# elysium_v0_1.net
KiCad netlist of a schematic drawn in EAGLE
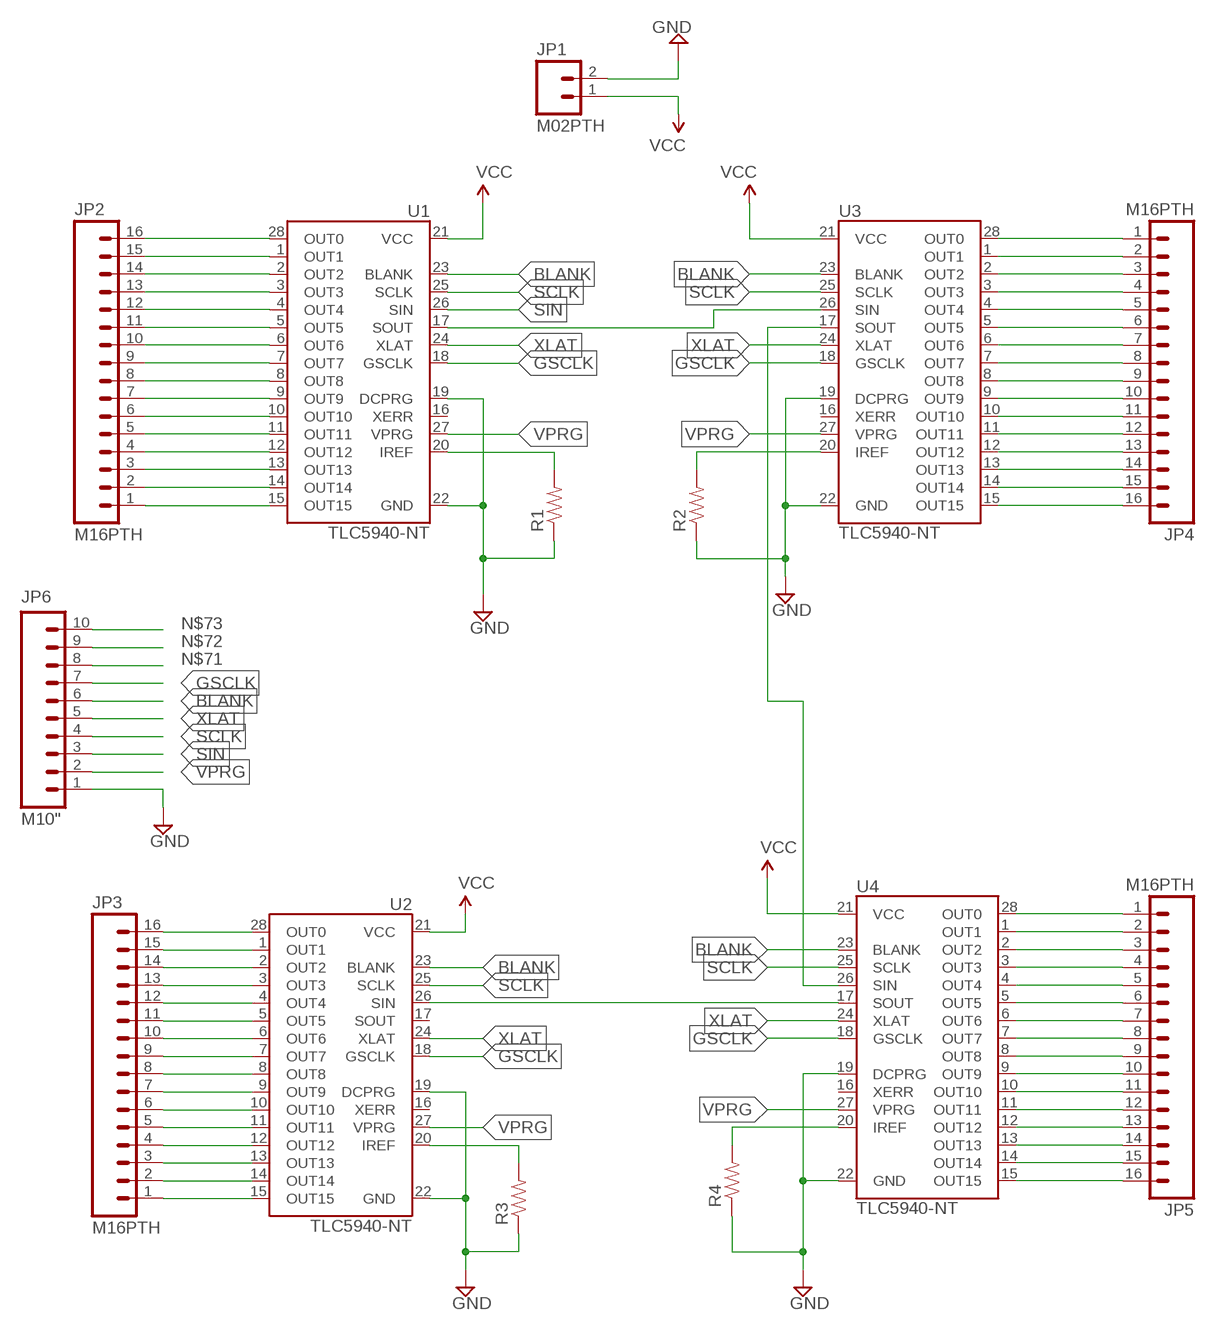
[diagram p0: schematic, sheet 1]

(export (version "E")
  (design (tool "Eeschema 10.0.6"))
  (components
    (comp (ref "JP1")
      (value "M02PTH")
      (footprint "eagle-import:1X02")
      (libsource (lib "eagle-import") (part "M02PTH"))
    )
    (comp (ref "JP2")
      (value "M16PTH")
      (footprint "eagle-import:1X16")
      (libsource (lib "eagle-import") (part "M16PTH"))
    )
    (comp (ref "JP3")
      (value "M16PTH")
      (footprint "eagle-import:1X16")
      (libsource (lib "eagle-import") (part "M16PTH"))
    )
    (comp (ref "JP4")
      (value "M16PTH")
      (footprint "eagle-import:1X16")
      (libsource (lib "eagle-import") (part "M16PTH"))
    )
    (comp (ref "JP5")
      (value "M16PTH")
      (footprint "eagle-import:1X16")
      (libsource (lib "eagle-import") (part "M16PTH"))
    )
    (comp (ref "JP6")
      (value "M10\"")
      (footprint "eagle-import:1X10")
      (libsource (lib "eagle-import") (part "M10{dblquote}"))
    )
    (comp (ref "R1")
      (value "RESISTOREZ")
      (footprint "eagle-import:AXIAL-0.3EZ")
      (libsource (lib "eagle-import") (part "RESISTOREZ"))
    )
    (comp (ref "R2")
      (value "RESISTOREZ")
      (footprint "eagle-import:AXIAL-0.3EZ")
      (libsource (lib "eagle-import") (part "RESISTOREZ"))
    )
    (comp (ref "R3")
      (value "RESISTOREZ")
      (footprint "eagle-import:AXIAL-0.3EZ")
      (libsource (lib "eagle-import") (part "RESISTOREZ"))
    )
    (comp (ref "R4")
      (value "RESISTOREZ")
      (footprint "eagle-import:AXIAL-0.3EZ")
      (libsource (lib "eagle-import") (part "RESISTOREZ"))
    )
    (comp (ref "U1")
      (value "TLC5940-NT")
      (footprint "eagle-import:DIL28-3")
      (libsource (lib "eagle-import") (part "TLC5940-NT"))
    )
    (comp (ref "U2")
      (value "TLC5940-NT")
      (footprint "eagle-import:DIL28-3")
      (libsource (lib "eagle-import") (part "TLC5940-NT"))
    )
    (comp (ref "U3")
      (value "TLC5940-NT")
      (footprint "eagle-import:DIL28-3")
      (libsource (lib "eagle-import") (part "TLC5940-NT"))
    )
    (comp (ref "U4")
      (value "TLC5940-NT")
      (footprint "eagle-import:DIL28-3")
      (libsource (lib "eagle-import") (part "TLC5940-NT"))
    )
  )
  (nets
    (net (code "1") (name "/N$71") (class "Default")
      (node (ref "JP6") (pin "8") (pinfunction "8_8") (pintype "passive"))
    )
    (net (code "2") (name "/N$72") (class "Default")
      (node (ref "JP6") (pin "9") (pinfunction "9_9") (pintype "passive"))
    )
    (net (code "3") (name "/N$73") (class "Default")
      (node (ref "JP6") (pin "10") (pinfunction "10_10") (pintype "passive"))
    )
    (net (code "4") (name "BLANK") (class "Default")
      (node (ref "JP6") (pin "6") (pinfunction "6_6") (pintype "passive"))
      (node (ref "U1") (pin "23") (pinfunction "BLANK_23") (pintype "bidirectional"))
      (node (ref "U2") (pin "23") (pinfunction "BLANK_23") (pintype "bidirectional"))
      (node (ref "U3") (pin "23") (pinfunction "BLANK_23") (pintype "bidirectional"))
      (node (ref "U4") (pin "23") (pinfunction "BLANK_23") (pintype "bidirectional"))
    )
    (net (code "5") (name "GND") (class "Default")
      (node (ref "JP1") (pin "2") (pinfunction "2_2") (pintype "passive"))
      (node (ref "JP6") (pin "1") (pinfunction "1_1") (pintype "passive"))
      (node (ref "R1") (pin "P$1") (pinfunction "1_P$1") (pintype "passive"))
      (node (ref "R2") (pin "P$1") (pinfunction "1_P$1") (pintype "passive"))
      (node (ref "R3") (pin "P$1") (pinfunction "1_P$1") (pintype "passive"))
      (node (ref "R4") (pin "P$1") (pinfunction "1_P$1") (pintype "passive"))
      (node (ref "U1") (pin "19") (pinfunction "DCPRG_19") (pintype "bidirectional"))
      (node (ref "U1") (pin "22") (pinfunction "GND_22") (pintype "bidirectional"))
      (node (ref "U2") (pin "19") (pinfunction "DCPRG_19") (pintype "bidirectional"))
      (node (ref "U2") (pin "22") (pinfunction "GND_22") (pintype "bidirectional"))
      (node (ref "U3") (pin "19") (pinfunction "DCPRG_19") (pintype "bidirectional"))
      (node (ref "U3") (pin "22") (pinfunction "GND_22") (pintype "bidirectional"))
      (node (ref "U4") (pin "19") (pinfunction "DCPRG_19") (pintype "bidirectional"))
      (node (ref "U4") (pin "22") (pinfunction "GND_22") (pintype "bidirectional"))
    )
    (net (code "6") (name "GSCLK") (class "Default")
      (node (ref "JP6") (pin "7") (pinfunction "7_7") (pintype "passive"))
      (node (ref "U1") (pin "18") (pinfunction "GSCLK_18") (pintype "bidirectional"))
      (node (ref "U2") (pin "18") (pinfunction "GSCLK_18") (pintype "bidirectional"))
      (node (ref "U3") (pin "18") (pinfunction "GSCLK_18") (pintype "bidirectional"))
      (node (ref "U4") (pin "18") (pinfunction "GSCLK_18") (pintype "bidirectional"))
    )
    (net (code "7") (name "Net-(R1-2)") (class "Default")
      (node (ref "R1") (pin "P$2") (pinfunction "2_P$2") (pintype "passive"))
      (node (ref "U1") (pin "20") (pinfunction "IREF_20") (pintype "bidirectional"))
    )
    (net (code "8") (name "Net-(R2-2)") (class "Default")
      (node (ref "R2") (pin "P$2") (pinfunction "2_P$2") (pintype "passive"))
      (node (ref "U3") (pin "20") (pinfunction "IREF_20") (pintype "bidirectional"))
    )
    (net (code "9") (name "Net-(R3-2)") (class "Default")
      (node (ref "R3") (pin "P$2") (pinfunction "2_P$2") (pintype "passive"))
      (node (ref "U2") (pin "20") (pinfunction "IREF_20") (pintype "bidirectional"))
    )
    (net (code "10") (name "Net-(R4-2)") (class "Default")
      (node (ref "R4") (pin "P$2") (pinfunction "2_P$2") (pintype "passive"))
      (node (ref "U4") (pin "20") (pinfunction "IREF_20") (pintype "bidirectional"))
    )
    (net (code "11") (name "Net-(U1-OUT0)") (class "Default")
      (node (ref "JP2") (pin "16") (pinfunction "16_16") (pintype "passive"))
      (node (ref "U1") (pin "28") (pinfunction "OUT0_28") (pintype "bidirectional"))
    )
    (net (code "12") (name "Net-(U1-OUT1)") (class "Default")
      (node (ref "JP2") (pin "15") (pinfunction "15_15") (pintype "passive"))
      (node (ref "U1") (pin "1") (pinfunction "OUT1_1") (pintype "bidirectional"))
    )
    (net (code "13") (name "Net-(U1-OUT2)") (class "Default")
      (node (ref "JP2") (pin "14") (pinfunction "14_14") (pintype "passive"))
      (node (ref "U1") (pin "2") (pinfunction "OUT2_2") (pintype "bidirectional"))
    )
    (net (code "14") (name "Net-(U1-OUT3)") (class "Default")
      (node (ref "JP2") (pin "13") (pinfunction "13_13") (pintype "passive"))
      (node (ref "U1") (pin "3") (pinfunction "OUT3_3") (pintype "bidirectional"))
    )
    (net (code "15") (name "Net-(U1-OUT4)") (class "Default")
      (node (ref "JP2") (pin "12") (pinfunction "12_12") (pintype "passive"))
      (node (ref "U1") (pin "4") (pinfunction "OUT4_4") (pintype "bidirectional"))
    )
    (net (code "16") (name "Net-(U1-OUT5)") (class "Default")
      (node (ref "JP2") (pin "11") (pinfunction "11_11") (pintype "passive"))
      (node (ref "U1") (pin "5") (pinfunction "OUT5_5") (pintype "bidirectional"))
    )
    (net (code "17") (name "Net-(U1-OUT6)") (class "Default")
      (node (ref "JP2") (pin "10") (pinfunction "10_10") (pintype "passive"))
      (node (ref "U1") (pin "6") (pinfunction "OUT6_6") (pintype "bidirectional"))
    )
    (net (code "18") (name "Net-(U1-OUT7)") (class "Default")
      (node (ref "JP2") (pin "9") (pinfunction "9_9") (pintype "passive"))
      (node (ref "U1") (pin "7") (pinfunction "OUT7_7") (pintype "bidirectional"))
    )
    (net (code "19") (name "Net-(U1-OUT8)") (class "Default")
      (node (ref "JP2") (pin "8") (pinfunction "8_8") (pintype "passive"))
      (node (ref "U1") (pin "8") (pinfunction "OUT8_8") (pintype "bidirectional"))
    )
    (net (code "20") (name "Net-(U1-OUT9)") (class "Default")
      (node (ref "JP2") (pin "7") (pinfunction "7_7") (pintype "passive"))
      (node (ref "U1") (pin "9") (pinfunction "OUT9_9") (pintype "bidirectional"))
    )
    (net (code "21") (name "Net-(U1-OUT10)") (class "Default")
      (node (ref "JP2") (pin "6") (pinfunction "6_6") (pintype "passive"))
      (node (ref "U1") (pin "10") (pinfunction "OUT10_10") (pintype "bidirectional"))
    )
    (net (code "22") (name "Net-(U1-OUT11)") (class "Default")
      (node (ref "JP2") (pin "5") (pinfunction "5_5") (pintype "passive"))
      (node (ref "U1") (pin "11") (pinfunction "OUT11_11") (pintype "bidirectional"))
    )
    (net (code "23") (name "Net-(U1-OUT12)") (class "Default")
      (node (ref "JP2") (pin "4") (pinfunction "4_4") (pintype "passive"))
      (node (ref "U1") (pin "12") (pinfunction "OUT12_12") (pintype "bidirectional"))
    )
    (net (code "24") (name "Net-(U1-OUT13)") (class "Default")
      (node (ref "JP2") (pin "3") (pinfunction "3_3") (pintype "passive"))
      (node (ref "U1") (pin "13") (pinfunction "OUT13_13") (pintype "bidirectional"))
    )
    (net (code "25") (name "Net-(U1-OUT14)") (class "Default")
      (node (ref "JP2") (pin "2") (pinfunction "2_2") (pintype "passive"))
      (node (ref "U1") (pin "14") (pinfunction "OUT14_14") (pintype "bidirectional"))
    )
    (net (code "26") (name "Net-(U1-OUT15)") (class "Default")
      (node (ref "JP2") (pin "1") (pinfunction "1_1") (pintype "passive"))
      (node (ref "U1") (pin "15") (pinfunction "OUT15_15") (pintype "bidirectional"))
    )
    (net (code "27") (name "Net-(U1-SOUT)") (class "Default")
      (node (ref "U1") (pin "17") (pinfunction "SOUT_17") (pintype "bidirectional"))
      (node (ref "U3") (pin "26") (pinfunction "SIN_26") (pintype "bidirectional"))
    )
    (net (code "28") (name "Net-(U2-OUT0)") (class "Default")
      (node (ref "JP3") (pin "16") (pinfunction "16_16") (pintype "passive"))
      (node (ref "U2") (pin "28") (pinfunction "OUT0_28") (pintype "bidirectional"))
    )
    (net (code "29") (name "Net-(U2-OUT1)") (class "Default")
      (node (ref "JP3") (pin "15") (pinfunction "15_15") (pintype "passive"))
      (node (ref "U2") (pin "1") (pinfunction "OUT1_1") (pintype "bidirectional"))
    )
    (net (code "30") (name "Net-(U2-OUT2)") (class "Default")
      (node (ref "JP3") (pin "14") (pinfunction "14_14") (pintype "passive"))
      (node (ref "U2") (pin "2") (pinfunction "OUT2_2") (pintype "bidirectional"))
    )
    (net (code "31") (name "Net-(U2-OUT3)") (class "Default")
      (node (ref "JP3") (pin "13") (pinfunction "13_13") (pintype "passive"))
      (node (ref "U2") (pin "3") (pinfunction "OUT3_3") (pintype "bidirectional"))
    )
    (net (code "32") (name "Net-(U2-OUT4)") (class "Default")
      (node (ref "JP3") (pin "12") (pinfunction "12_12") (pintype "passive"))
      (node (ref "U2") (pin "4") (pinfunction "OUT4_4") (pintype "bidirectional"))
    )
    (net (code "33") (name "Net-(U2-OUT5)") (class "Default")
      (node (ref "JP3") (pin "11") (pinfunction "11_11") (pintype "passive"))
      (node (ref "U2") (pin "5") (pinfunction "OUT5_5") (pintype "bidirectional"))
    )
    (net (code "34") (name "Net-(U2-OUT6)") (class "Default")
      (node (ref "JP3") (pin "10") (pinfunction "10_10") (pintype "passive"))
      (node (ref "U2") (pin "6") (pinfunction "OUT6_6") (pintype "bidirectional"))
    )
    (net (code "35") (name "Net-(U2-OUT7)") (class "Default")
      (node (ref "JP3") (pin "9") (pinfunction "9_9") (pintype "passive"))
      (node (ref "U2") (pin "7") (pinfunction "OUT7_7") (pintype "bidirectional"))
    )
    (net (code "36") (name "Net-(U2-OUT8)") (class "Default")
      (node (ref "JP3") (pin "8") (pinfunction "8_8") (pintype "passive"))
      (node (ref "U2") (pin "8") (pinfunction "OUT8_8") (pintype "bidirectional"))
    )
    (net (code "37") (name "Net-(U2-OUT9)") (class "Default")
      (node (ref "JP3") (pin "7") (pinfunction "7_7") (pintype "passive"))
      (node (ref "U2") (pin "9") (pinfunction "OUT9_9") (pintype "bidirectional"))
    )
    (net (code "38") (name "Net-(U2-OUT10)") (class "Default")
      (node (ref "JP3") (pin "6") (pinfunction "6_6") (pintype "passive"))
      (node (ref "U2") (pin "10") (pinfunction "OUT10_10") (pintype "bidirectional"))
    )
    (net (code "39") (name "Net-(U2-OUT11)") (class "Default")
      (node (ref "JP3") (pin "5") (pinfunction "5_5") (pintype "passive"))
      (node (ref "U2") (pin "11") (pinfunction "OUT11_11") (pintype "bidirectional"))
    )
    (net (code "40") (name "Net-(U2-OUT12)") (class "Default")
      (node (ref "JP3") (pin "4") (pinfunction "4_4") (pintype "passive"))
      (node (ref "U2") (pin "12") (pinfunction "OUT12_12") (pintype "bidirectional"))
    )
    (net (code "41") (name "Net-(U2-OUT13)") (class "Default")
      (node (ref "JP3") (pin "3") (pinfunction "3_3") (pintype "passive"))
      (node (ref "U2") (pin "13") (pinfunction "OUT13_13") (pintype "bidirectional"))
    )
    (net (code "42") (name "Net-(U2-OUT14)") (class "Default")
      (node (ref "JP3") (pin "2") (pinfunction "2_2") (pintype "passive"))
      (node (ref "U2") (pin "14") (pinfunction "OUT14_14") (pintype "bidirectional"))
    )
    (net (code "43") (name "Net-(U2-OUT15)") (class "Default")
      (node (ref "JP3") (pin "1") (pinfunction "1_1") (pintype "passive"))
      (node (ref "U2") (pin "15") (pinfunction "OUT15_15") (pintype "bidirectional"))
    )
    (net (code "44") (name "Net-(U2-SIN)") (class "Default")
      (node (ref "U2") (pin "26") (pinfunction "SIN_26") (pintype "bidirectional"))
      (node (ref "U4") (pin "17") (pinfunction "SOUT_17") (pintype "bidirectional"))
    )
    (net (code "45") (name "Net-(U3-OUT0)") (class "Default")
      (node (ref "JP4") (pin "1") (pinfunction "1_1") (pintype "passive"))
      (node (ref "U3") (pin "28") (pinfunction "OUT0_28") (pintype "bidirectional"))
    )
    (net (code "46") (name "Net-(U3-OUT1)") (class "Default")
      (node (ref "JP4") (pin "2") (pinfunction "2_2") (pintype "passive"))
      (node (ref "U3") (pin "1") (pinfunction "OUT1_1") (pintype "bidirectional"))
    )
    (net (code "47") (name "Net-(U3-OUT2)") (class "Default")
      (node (ref "JP4") (pin "3") (pinfunction "3_3") (pintype "passive"))
      (node (ref "U3") (pin "2") (pinfunction "OUT2_2") (pintype "bidirectional"))
    )
    (net (code "48") (name "Net-(U3-OUT3)") (class "Default")
      (node (ref "JP4") (pin "4") (pinfunction "4_4") (pintype "passive"))
      (node (ref "U3") (pin "3") (pinfunction "OUT3_3") (pintype "bidirectional"))
    )
    (net (code "49") (name "Net-(U3-OUT4)") (class "Default")
      (node (ref "JP4") (pin "5") (pinfunction "5_5") (pintype "passive"))
      (node (ref "U3") (pin "4") (pinfunction "OUT4_4") (pintype "bidirectional"))
    )
    (net (code "50") (name "Net-(U3-OUT5)") (class "Default")
      (node (ref "JP4") (pin "6") (pinfunction "6_6") (pintype "passive"))
      (node (ref "U3") (pin "5") (pinfunction "OUT5_5") (pintype "bidirectional"))
    )
    (net (code "51") (name "Net-(U3-OUT6)") (class "Default")
      (node (ref "JP4") (pin "7") (pinfunction "7_7") (pintype "passive"))
      (node (ref "U3") (pin "6") (pinfunction "OUT6_6") (pintype "bidirectional"))
    )
    (net (code "52") (name "Net-(U3-OUT7)") (class "Default")
      (node (ref "JP4") (pin "8") (pinfunction "8_8") (pintype "passive"))
      (node (ref "U3") (pin "7") (pinfunction "OUT7_7") (pintype "bidirectional"))
    )
    (net (code "53") (name "Net-(U3-OUT8)") (class "Default")
      (node (ref "JP4") (pin "9") (pinfunction "9_9") (pintype "passive"))
      (node (ref "U3") (pin "8") (pinfunction "OUT8_8") (pintype "bidirectional"))
    )
    (net (code "54") (name "Net-(U3-OUT9)") (class "Default")
      (node (ref "JP4") (pin "10") (pinfunction "10_10") (pintype "passive"))
      (node (ref "U3") (pin "9") (pinfunction "OUT9_9") (pintype "bidirectional"))
    )
    (net (code "55") (name "Net-(U3-OUT10)") (class "Default")
      (node (ref "JP4") (pin "11") (pinfunction "11_11") (pintype "passive"))
      (node (ref "U3") (pin "10") (pinfunction "OUT10_10") (pintype "bidirectional"))
    )
    (net (code "56") (name "Net-(U3-OUT11)") (class "Default")
      (node (ref "JP4") (pin "12") (pinfunction "12_12") (pintype "passive"))
      (node (ref "U3") (pin "11") (pinfunction "OUT11_11") (pintype "bidirectional"))
    )
    (net (code "57") (name "Net-(U3-OUT12)") (class "Default")
      (node (ref "JP4") (pin "13") (pinfunction "13_13") (pintype "passive"))
      (node (ref "U3") (pin "12") (pinfunction "OUT12_12") (pintype "bidirectional"))
    )
    (net (code "58") (name "Net-(U3-OUT13)") (class "Default")
      (node (ref "JP4") (pin "14") (pinfunction "14_14") (pintype "passive"))
      (node (ref "U3") (pin "13") (pinfunction "OUT13_13") (pintype "bidirectional"))
    )
    (net (code "59") (name "Net-(U3-OUT14)") (class "Default")
      (node (ref "JP4") (pin "15") (pinfunction "15_15") (pintype "passive"))
      (node (ref "U3") (pin "14") (pinfunction "OUT14_14") (pintype "bidirectional"))
    )
    (net (code "60") (name "Net-(U3-OUT15)") (class "Default")
      (node (ref "JP4") (pin "16") (pinfunction "16_16") (pintype "passive"))
      (node (ref "U3") (pin "15") (pinfunction "OUT15_15") (pintype "bidirectional"))
    )
    (net (code "61") (name "Net-(U3-SOUT)") (class "Default")
      (node (ref "U3") (pin "17") (pinfunction "SOUT_17") (pintype "bidirectional"))
      (node (ref "U4") (pin "26") (pinfunction "SIN_26") (pintype "bidirectional"))
    )
    (net (code "62") (name "Net-(U4-OUT0)") (class "Default")
      (node (ref "JP5") (pin "1") (pinfunction "1_1") (pintype "passive"))
      (node (ref "U4") (pin "28") (pinfunction "OUT0_28") (pintype "bidirectional"))
    )
    (net (code "63") (name "Net-(U4-OUT1)") (class "Default")
      (node (ref "JP5") (pin "2") (pinfunction "2_2") (pintype "passive"))
      (node (ref "U4") (pin "1") (pinfunction "OUT1_1") (pintype "bidirectional"))
    )
    (net (code "64") (name "Net-(U4-OUT2)") (class "Default")
      (node (ref "JP5") (pin "3") (pinfunction "3_3") (pintype "passive"))
      (node (ref "U4") (pin "2") (pinfunction "OUT2_2") (pintype "bidirectional"))
    )
    (net (code "65") (name "Net-(U4-OUT3)") (class "Default")
      (node (ref "JP5") (pin "4") (pinfunction "4_4") (pintype "passive"))
      (node (ref "U4") (pin "3") (pinfunction "OUT3_3") (pintype "bidirectional"))
    )
    (net (code "66") (name "Net-(U4-OUT4)") (class "Default")
      (node (ref "JP5") (pin "5") (pinfunction "5_5") (pintype "passive"))
      (node (ref "U4") (pin "4") (pinfunction "OUT4_4") (pintype "bidirectional"))
    )
    (net (code "67") (name "Net-(U4-OUT5)") (class "Default")
      (node (ref "JP5") (pin "6") (pinfunction "6_6") (pintype "passive"))
      (node (ref "U4") (pin "5") (pinfunction "OUT5_5") (pintype "bidirectional"))
    )
    (net (code "68") (name "Net-(U4-OUT6)") (class "Default")
      (node (ref "JP5") (pin "7") (pinfunction "7_7") (pintype "passive"))
      (node (ref "U4") (pin "6") (pinfunction "OUT6_6") (pintype "bidirectional"))
    )
    (net (code "69") (name "Net-(U4-OUT7)") (class "Default")
      (node (ref "JP5") (pin "8") (pinfunction "8_8") (pintype "passive"))
      (node (ref "U4") (pin "7") (pinfunction "OUT7_7") (pintype "bidirectional"))
    )
    (net (code "70") (name "Net-(U4-OUT8)") (class "Default")
      (node (ref "JP5") (pin "9") (pinfunction "9_9") (pintype "passive"))
      (node (ref "U4") (pin "8") (pinfunction "OUT8_8") (pintype "bidirectional"))
    )
    (net (code "71") (name "Net-(U4-OUT9)") (class "Default")
      (node (ref "JP5") (pin "10") (pinfunction "10_10") (pintype "passive"))
      (node (ref "U4") (pin "9") (pinfunction "OUT9_9") (pintype "bidirectional"))
    )
    (net (code "72") (name "Net-(U4-OUT10)") (class "Default")
      (node (ref "JP5") (pin "11") (pinfunction "11_11") (pintype "passive"))
      (node (ref "U4") (pin "10") (pinfunction "OUT10_10") (pintype "bidirectional"))
    )
    (net (code "73") (name "Net-(U4-OUT11)") (class "Default")
      (node (ref "JP5") (pin "12") (pinfunction "12_12") (pintype "passive"))
      (node (ref "U4") (pin "11") (pinfunction "OUT11_11") (pintype "bidirectional"))
    )
    (net (code "74") (name "Net-(U4-OUT12)") (class "Default")
      (node (ref "JP5") (pin "13") (pinfunction "13_13") (pintype "passive"))
      (node (ref "U4") (pin "12") (pinfunction "OUT12_12") (pintype "bidirectional"))
    )
    (net (code "75") (name "Net-(U4-OUT13)") (class "Default")
      (node (ref "JP5") (pin "14") (pinfunction "14_14") (pintype "passive"))
      (node (ref "U4") (pin "13") (pinfunction "OUT13_13") (pintype "bidirectional"))
    )
    (net (code "76") (name "Net-(U4-OUT14)") (class "Default")
      (node (ref "JP5") (pin "15") (pinfunction "15_15") (pintype "passive"))
      (node (ref "U4") (pin "14") (pinfunction "OUT14_14") (pintype "bidirectional"))
    )
    (net (code "77") (name "Net-(U4-OUT15)") (class "Default")
      (node (ref "JP5") (pin "16") (pinfunction "16_16") (pintype "passive"))
      (node (ref "U4") (pin "15") (pinfunction "OUT15_15") (pintype "bidirectional"))
    )
    (net (code "78") (name "SCLK") (class "Default")
      (node (ref "JP6") (pin "4") (pinfunction "4_4") (pintype "passive"))
      (node (ref "U1") (pin "25") (pinfunction "SCLK_25") (pintype "bidirectional"))
      (node (ref "U2") (pin "25") (pinfunction "SCLK_25") (pintype "bidirectional"))
      (node (ref "U3") (pin "25") (pinfunction "SCLK_25") (pintype "bidirectional"))
      (node (ref "U4") (pin "25") (pinfunction "SCLK_25") (pintype "bidirectional"))
    )
    (net (code "79") (name "SIN") (class "Default")
      (node (ref "JP6") (pin "3") (pinfunction "3_3") (pintype "passive"))
      (node (ref "U1") (pin "26") (pinfunction "SIN_26") (pintype "bidirectional"))
    )
    (net (code "80") (name "VCC") (class "Default")
      (node (ref "JP1") (pin "1") (pinfunction "1_1") (pintype "passive"))
      (node (ref "U1") (pin "21") (pinfunction "VCC_21") (pintype "bidirectional"))
      (node (ref "U2") (pin "21") (pinfunction "VCC_21") (pintype "bidirectional"))
      (node (ref "U3") (pin "21") (pinfunction "VCC_21") (pintype "bidirectional"))
      (node (ref "U4") (pin "21") (pinfunction "VCC_21") (pintype "bidirectional"))
    )
    (net (code "81") (name "VPRG") (class "Default")
      (node (ref "JP6") (pin "2") (pinfunction "2_2") (pintype "passive"))
      (node (ref "U1") (pin "27") (pinfunction "VPRG_27") (pintype "bidirectional"))
      (node (ref "U2") (pin "27") (pinfunction "VPRG_27") (pintype "bidirectional"))
      (node (ref "U3") (pin "27") (pinfunction "VPRG_27") (pintype "bidirectional"))
      (node (ref "U4") (pin "27") (pinfunction "VPRG_27") (pintype "bidirectional"))
    )
    (net (code "82") (name "XLAT") (class "Default")
      (node (ref "JP6") (pin "5") (pinfunction "5_5") (pintype "passive"))
      (node (ref "U1") (pin "24") (pinfunction "XLAT_24") (pintype "bidirectional"))
      (node (ref "U2") (pin "24") (pinfunction "XLAT_24") (pintype "bidirectional"))
      (node (ref "U3") (pin "24") (pinfunction "XLAT_24") (pintype "bidirectional"))
      (node (ref "U4") (pin "24") (pinfunction "XLAT_24") (pintype "bidirectional"))
    )
    (net (code "83") (name "unconnected-(U1-XERR-Pad16)") (class "Default")
      (node (ref "U1") (pin "16") (pinfunction "XERR_16") (pintype "bidirectional"))
    )
    (net (code "84") (name "unconnected-(U2-SOUT-Pad17)") (class "Default")
      (node (ref "U2") (pin "17") (pinfunction "SOUT_17") (pintype "bidirectional"))
    )
    (net (code "85") (name "unconnected-(U2-XERR-Pad16)") (class "Default")
      (node (ref "U2") (pin "16") (pinfunction "XERR_16") (pintype "bidirectional"))
    )
    (net (code "86") (name "unconnected-(U3-XERR-Pad16)") (class "Default")
      (node (ref "U3") (pin "16") (pinfunction "XERR_16") (pintype "bidirectional"))
    )
    (net (code "87") (name "unconnected-(U4-XERR-Pad16)") (class "Default")
      (node (ref "U4") (pin "16") (pinfunction "XERR_16") (pintype "bidirectional"))
    )
  )
)
